# Low_Power_Brushed_Motor_Controller.net
KiCad netlist of a schematic drawn in Altium Designer
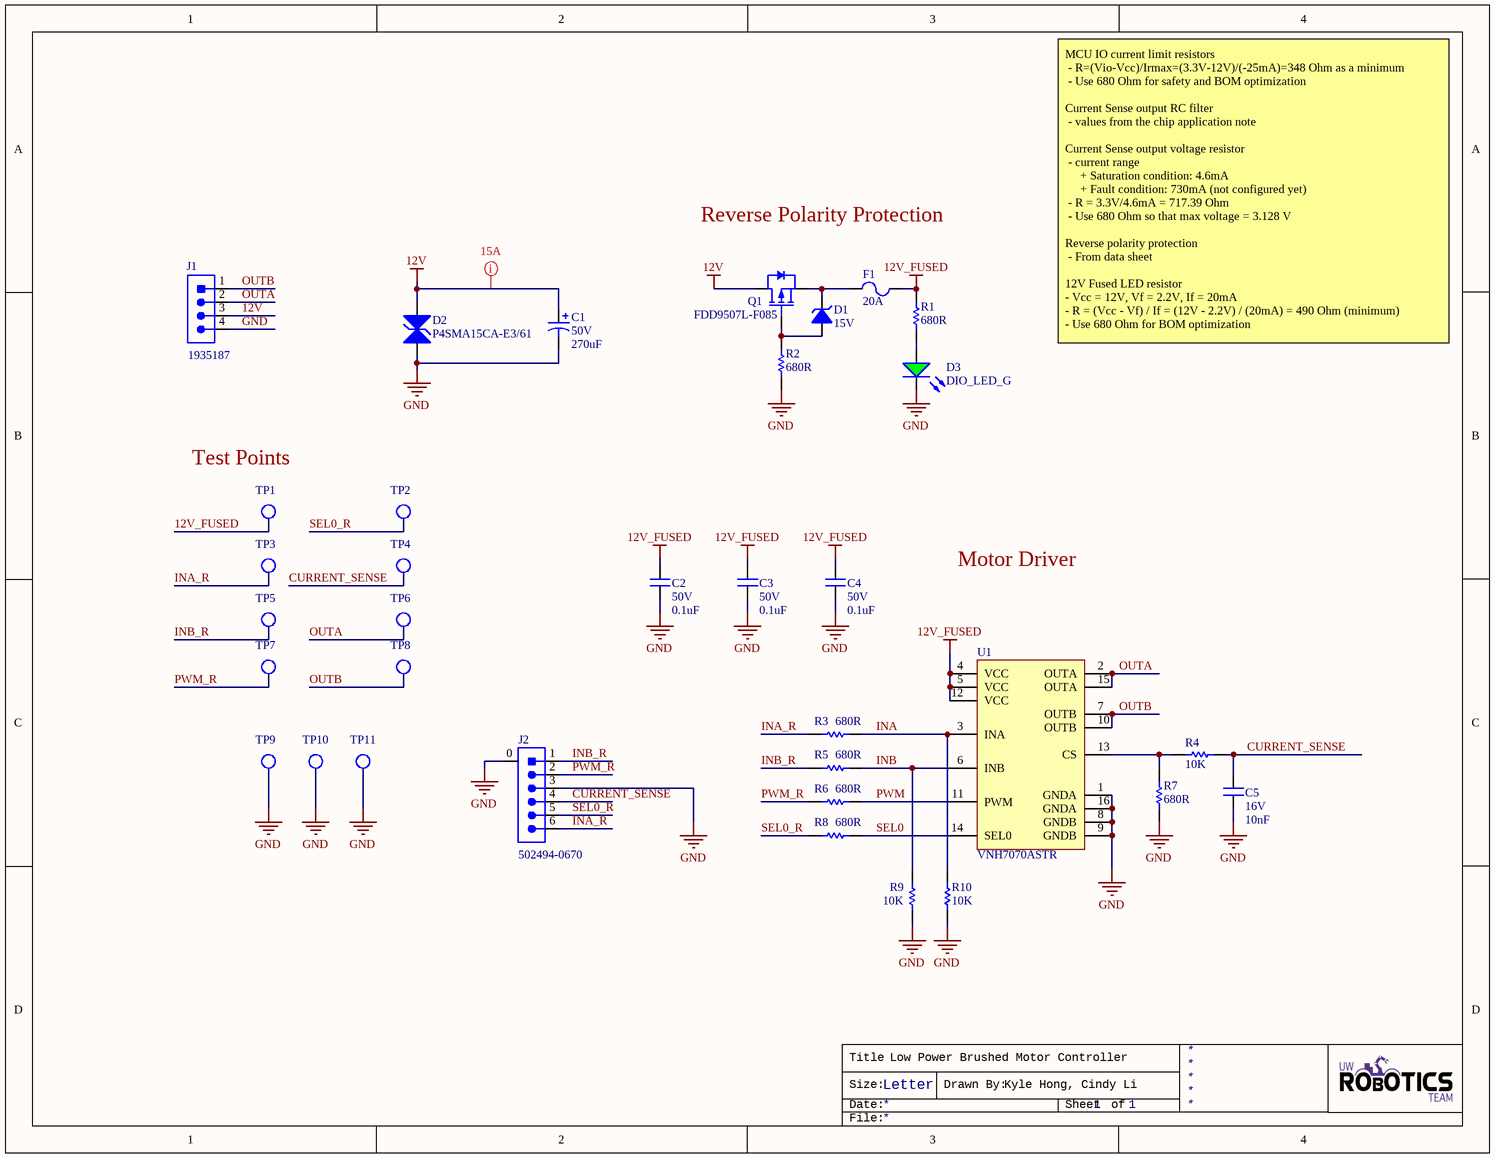
[diagram p0: Low Power Brushed Motor Controller.SchDoc]

(export (version "E")
  (design (tool "Eeschema 10.0.6"))
  (components
    (comp (ref "C1")
      (value "CAP_270uF_50V_ALUM")
      (footprint "RADIAL_PANASONIC_G")
      (description "CAP ALUM 270UF 20% 50V RADIAL")
      (fields
        (field (name "TOLERANCE") "20%")
        (field (name "VOLTAGE RATING") "50V")
        (field (name "CAPACITANCE") "270uF")
      )
      (libsource (lib "UWRT_Schematic_Library_2020") (part "CAP_270uF_50V_ALUM"))
    )
    (comp (ref "C2")
      (value "0.1uF")
      (footprint "CAPC0603(1608)55_N")
      (description "CAP CER 0.1UF 50V X7R 0603")
      (fields (field (name "VOLTAGE RATING") "50V") (field (name "Comment") "CAP_0.1uF_50V_0603"))
      (libsource (lib "UWRT_Schematic_Library_2020") (part "CAP_0.1uF_50V_0603"))
    )
    (comp (ref "C3")
      (value "0.1uF")
      (footprint "CAPC0603(1608)55_N")
      (description "CAP CER 0.1UF 50V X7R 0603")
      (fields (field (name "VOLTAGE RATING") "50V") (field (name "Comment") "CAP_0.1uF_50V_0603"))
      (libsource (lib "UWRT_Schematic_Library_2020") (part "CAP_0.1uF_50V_0603"))
    )
    (comp (ref "C4")
      (value "0.1uF")
      (footprint "CAPC0603(1608)55_N")
      (description "CAP CER 0.1UF 50V X7R 0603")
      (fields (field (name "VOLTAGE RATING") "50V") (field (name "Comment") "CAP_0.1uF_50V_0603"))
      (libsource (lib "UWRT_Schematic_Library_2020") (part "CAP_0.1uF_50V_0603"))
    )
    (comp (ref "C5")
      (value "10nF")
      (footprint "CAPC0603(1608)55_N")
      (description "CAP CER 10000PF 16V X7R 0603")
      (fields (field (name "VOLTAGE RATING") "16V") (field (name "Comment") "CAP_10nF_0603"))
      (libsource (lib "UWRT_Schematic_Library_2020") (part "CAP_10nF_0603"))
    )
    (comp (ref "D1")
      (value "DIO_ZENER_15V")
      (footprint "SOD-323_UNIDIR")
      (description "DIODE ZENER 15V 300mW SMD SOD-323")
      (fields (field (name "TOLERANCE") "5%") (field (name "WORKING VOLTAGE") "15V"))
      (libsource (lib "UWRT_Schematic_Library_2020") (part "DIO_ZENER_15V"))
    )
    (comp (ref "D2")
      (value "TVS_DIODE_BIDIR_12.8V")
      (footprint "TVS_DIODE_BIDIR_DO-214AC_SMA")
      (description "TVS DIODE 12.8V 21.2V SMA")
      (fields (field (name "MANUFACTURER PART NUMBER 1") "P4SMA15CA-E3/61"))
      (libsource (lib "UWRT_Schematic_Library_2020") (part "TVS_DIODE_BIDIR_12.8V"))
    )
    (comp (ref "D3")
      (value "DIO_LED_G")
      (footprint "LED_0805_LINE")
      (description "LED GREEN DIFFUSED 0805 SMD")
      (fields (field (name "MPN") "LG R971-KN-1") (field (name "MANUFACTURER") "OSRAM"))
      (libsource (lib "UWRT_Schematic_Library_2020") (part "DIO_LED_G"))
    )
    (comp (ref "F1")
      (value "FUSE_20A_1206")
      (footprint "FUSE_1206")
      (fields (field (name "CURRENT RATING") "20A"))
      (libsource (lib "UWRT_Schematic_Library_2020") (part "FUSE_20A_1206"))
    )
    (comp (ref "J1")
      (value "CON_4M_TERM")
      (footprint "UWRT_Footprint_Library_2020:1935187")
      (description "TERM BLK 4POS SIDE ENTRY 5MM PCB")
      (fields (field (name "MANUFACTURER PART NUMBER 1") "1935187") (field (name "VOLTAGE") "300V"))
      (libsource (lib "UWRT_Schematic_Library_2020") (part "CON_4M_TERM"))
    )
    (comp (ref "J2")
      (value "CON_6M_SM_RA")
      (footprint "MOLEX-5024940670")
      (description "CONN HEADER SMD RIGHT ANGLE 2MM PITCH")
      (fields (field (name "MANUFACTURER PART NUMBER 1") "502494-0670"))
      (libsource (lib "UWRT_Schematic_Library_2020") (part "CON_6M_SM_RA"))
    )
    (comp (ref "Q1")
      (value "PMOS_40V_100A")
      (footprint "D-PAK")
      (description "MOSFET P-CH 40V 100A D-PAK 4.4MOHM")
      (fields (field (name "MANUFACTURER PART NUMBER 1") "FDD9507L-F085"))
      (libsource (lib "UWRT_Schematic_Library_2020") (part "PMOS_40V_100A"))
    )
    (comp (ref "R1")
      (value "RES_680R_0603")
      (footprint "RESC0603(1608)_N")
      (description "RES SMD 680 OHM 5% 0.1W 0603")
      (fields (field (name "TOLERANCE") "5%") (field (name "RESISTANCE") "680R"))
      (libsource (lib "UWRT_Schematic_Library_2020") (part "RES_680R_0603"))
    )
    (comp (ref "R2")
      (value "RES_680R_0603")
      (footprint "RESC0603(1608)_N")
      (description "RES SMD 680 OHM 5% 0.1W 0603")
      (fields (field (name "TOLERANCE") "5%") (field (name "RESISTANCE") "680R"))
      (libsource (lib "UWRT_Schematic_Library_2020") (part "RES_680R_0603"))
    )
    (comp (ref "R3")
      (value "RES_680R_0603")
      (footprint "RESC0603(1608)_N")
      (description "RES SMD 680 OHM 5% 0.1W 0603")
      (fields (field (name "TOLERANCE") "5%") (field (name "RESISTANCE") "680R"))
      (libsource (lib "UWRT_Schematic_Library_2020") (part "RES_680R_0603"))
    )
    (comp (ref "R4")
      (value "10K")
      (footprint "RESC0603(1608)_N")
      (description "RES SMD 10K OHM 5% 1/10W 0603")
      (fields (field (name "TOLERANCE") "5%") (field (name "Comment") "RES_10K_0603"))
      (libsource (lib "UWRT_Schematic_Library_2020") (part "RES_10K_0603"))
    )
    (comp (ref "R5")
      (value "RES_680R_0603")
      (footprint "RESC0603(1608)_N")
      (description "RES SMD 680 OHM 5% 0.1W 0603")
      (fields (field (name "TOLERANCE") "5%") (field (name "RESISTANCE") "680R"))
      (libsource (lib "UWRT_Schematic_Library_2020") (part "RES_680R_0603"))
    )
    (comp (ref "R6")
      (value "RES_680R_0603")
      (footprint "RESC0603(1608)_N")
      (description "RES SMD 680 OHM 5% 0.1W 0603")
      (fields (field (name "TOLERANCE") "5%") (field (name "RESISTANCE") "680R"))
      (libsource (lib "UWRT_Schematic_Library_2020") (part "RES_680R_0603"))
    )
    (comp (ref "R7")
      (value "RES_680R_0603")
      (footprint "RESC0603(1608)_N")
      (description "RES SMD 680 OHM 5% 0.1W 0603")
      (fields (field (name "TOLERANCE") "5%") (field (name "RESISTANCE") "680R"))
      (libsource (lib "UWRT_Schematic_Library_2020") (part "RES_680R_0603"))
    )
    (comp (ref "R8")
      (value "RES_680R_0603")
      (footprint "RESC0603(1608)_N")
      (description "RES SMD 680 OHM 5% 0.1W 0603")
      (fields (field (name "TOLERANCE") "5%") (field (name "RESISTANCE") "680R"))
      (libsource (lib "UWRT_Schematic_Library_2020") (part "RES_680R_0603"))
    )
    (comp (ref "R9")
      (value "10K")
      (footprint "RESC0603(1608)_N")
      (description "RES SMD 10K OHM 5% 1/10W 0603")
      (fields (field (name "TOLERANCE") "5%") (field (name "Comment") "RES_10K_0603"))
      (libsource (lib "UWRT_Schematic_Library_2020") (part "RES_10K_0603"))
    )
    (comp (ref "R10")
      (value "10K")
      (footprint "RESC0603(1608)_N")
      (description "RES SMD 10K OHM 5% 1/10W 0603")
      (fields (field (name "TOLERANCE") "5%") (field (name "Comment") "RES_10K_0603"))
      (libsource (lib "UWRT_Schematic_Library_2020") (part "RES_10K_0603"))
    )
    (comp (ref "TP1")
      (value "TESTPOINT_LOOP")
      (footprint "TESTPOINT_LOOP")
      (description "Loop testpoint through-hole pad")
      (fields (field (name "MANUFACTURER") "Keystone Electronics"))
      (libsource (lib "UWRT_Schematic_Library_2020") (part "TESTPOINT_LOOP"))
    )
    (comp (ref "TP2")
      (value "TESTPOINT_LOOP")
      (footprint "TESTPOINT_LOOP")
      (description "Loop testpoint through-hole pad")
      (fields (field (name "MANUFACTURER") "Keystone Electronics"))
      (libsource (lib "UWRT_Schematic_Library_2020") (part "TESTPOINT_LOOP"))
    )
    (comp (ref "TP3")
      (value "TESTPOINT_LOOP")
      (footprint "TESTPOINT_LOOP")
      (description "Loop testpoint through-hole pad")
      (fields (field (name "MANUFACTURER") "Keystone Electronics"))
      (libsource (lib "UWRT_Schematic_Library_2020") (part "TESTPOINT_LOOP"))
    )
    (comp (ref "TP4")
      (value "TESTPOINT_LOOP")
      (footprint "TESTPOINT_LOOP")
      (description "Loop testpoint through-hole pad")
      (fields (field (name "MANUFACTURER") "Keystone Electronics"))
      (libsource (lib "UWRT_Schematic_Library_2020") (part "TESTPOINT_LOOP"))
    )
    (comp (ref "TP5")
      (value "TESTPOINT_LOOP")
      (footprint "TESTPOINT_LOOP")
      (description "Loop testpoint through-hole pad")
      (fields (field (name "MANUFACTURER") "Keystone Electronics"))
      (libsource (lib "UWRT_Schematic_Library_2020") (part "TESTPOINT_LOOP"))
    )
    (comp (ref "TP6")
      (value "TESTPOINT_LOOP")
      (footprint "TESTPOINT_LOOP")
      (description "Loop testpoint through-hole pad")
      (fields (field (name "MANUFACTURER") "Keystone Electronics"))
      (libsource (lib "UWRT_Schematic_Library_2020") (part "TESTPOINT_LOOP"))
    )
    (comp (ref "TP7")
      (value "TESTPOINT_LOOP")
      (footprint "TESTPOINT_LOOP")
      (description "Loop testpoint through-hole pad")
      (fields (field (name "MANUFACTURER") "Keystone Electronics"))
      (libsource (lib "UWRT_Schematic_Library_2020") (part "TESTPOINT_LOOP"))
    )
    (comp (ref "TP8")
      (value "TESTPOINT_LOOP")
      (footprint "TESTPOINT_LOOP")
      (description "Loop testpoint through-hole pad")
      (fields (field (name "MANUFACTURER") "Keystone Electronics"))
      (libsource (lib "UWRT_Schematic_Library_2020") (part "TESTPOINT_LOOP"))
    )
    (comp (ref "TP9")
      (value "TESTPOINT_LOOP")
      (footprint "TESTPOINT_LOOP")
      (description "Loop testpoint through-hole pad")
      (fields (field (name "MANUFACTURER") "Keystone Electronics"))
      (libsource (lib "UWRT_Schematic_Library_2020") (part "TESTPOINT_LOOP"))
    )
    (comp (ref "TP10")
      (value "TESTPOINT_LOOP")
      (footprint "TESTPOINT_LOOP")
      (description "Loop testpoint through-hole pad")
      (fields (field (name "MANUFACTURER") "Keystone Electronics"))
      (libsource (lib "UWRT_Schematic_Library_2020") (part "TESTPOINT_LOOP"))
    )
    (comp (ref "TP11")
      (value "TESTPOINT_LOOP")
      (footprint "TESTPOINT_LOOP")
      (description "Loop testpoint through-hole pad")
      (fields (field (name "MANUFACTURER") "Keystone Electronics"))
      (libsource (lib "UWRT_Schematic_Library_2020") (part "TESTPOINT_LOOP"))
    )
    (comp (ref "U1")
      (value "IC_MOTOR_DRIVER_ST")
      (footprint "SO-16N")
      (description "IC H-BRIDGE MOTOR DRIVER 16-PINS STMicroelectronics VNH7070ASTR, SOIC")
      (fields (field (name "MANUFACTURER PART NUMBER 1") "VNH7070ASTR"))
      (libsource (lib "UWRT_Schematic_Library_2020") (part "IC_MOTOR_DRIVER_ST"))
    )
  )
  (nets
    (net (code "1") (name "/CURRENT_SENSE") (class "Default")
      (node (ref "C5") (pin "2") (pinfunction "2_2") (pintype "passive"))
      (node (ref "J2") (pin "4") (pinfunction "4_4") (pintype "passive"))
      (node (ref "R4") (pin "2") (pinfunction "2_2") (pintype "passive"))
      (node (ref "TP4") (pin "1") (pintype "passive"))
    )
    (net (code "2") (name "/INA") (class "Default")
      (node (ref "R10") (pin "2") (pinfunction "2_2") (pintype "passive"))
      (node (ref "R3") (pin "2") (pinfunction "2_2") (pintype "passive"))
      (node (ref "U1") (pin "3") (pinfunction "INA_3") (pintype "passive"))
    )
    (net (code "3") (name "/INA_R") (class "Default")
      (node (ref "J2") (pin "6") (pinfunction "6_6") (pintype "passive"))
      (node (ref "R3") (pin "1") (pinfunction "1_1") (pintype "passive"))
      (node (ref "TP3") (pin "1") (pintype "passive"))
    )
    (net (code "4") (name "/INB") (class "Default")
      (node (ref "R5") (pin "2") (pinfunction "2_2") (pintype "passive"))
      (node (ref "R9") (pin "2") (pinfunction "2_2") (pintype "passive"))
      (node (ref "U1") (pin "6") (pinfunction "INB_6") (pintype "passive"))
    )
    (net (code "5") (name "/INB_R") (class "Default")
      (node (ref "J2") (pin "1") (pinfunction "1_1") (pintype "passive"))
      (node (ref "R5") (pin "1") (pinfunction "1_1") (pintype "passive"))
      (node (ref "TP5") (pin "1") (pintype "passive"))
    )
    (net (code "6") (name "/OUTA") (class "Default")
      (node (ref "J1") (pin "2") (pinfunction "2_2") (pintype "passive"))
      (node (ref "TP6") (pin "1") (pintype "passive"))
      (node (ref "U1") (pin "15") (pinfunction "OUTA_15") (pintype "passive"))
      (node (ref "U1") (pin "2") (pinfunction "OUTA_2") (pintype "passive"))
    )
    (net (code "7") (name "/OUTB") (class "Default")
      (node (ref "J1") (pin "1") (pinfunction "1_1") (pintype "passive"))
      (node (ref "TP8") (pin "1") (pintype "passive"))
      (node (ref "U1") (pin "10") (pinfunction "OUTB_10") (pintype "passive"))
      (node (ref "U1") (pin "7") (pinfunction "OUTB_7") (pintype "passive"))
    )
    (net (code "8") (name "/PWM") (class "Default")
      (node (ref "R6") (pin "2") (pinfunction "2_2") (pintype "passive"))
      (node (ref "U1") (pin "11") (pinfunction "PWM_11") (pintype "passive"))
    )
    (net (code "9") (name "/PWM_R") (class "Default")
      (node (ref "J2") (pin "2") (pinfunction "2_2") (pintype "passive"))
      (node (ref "R6") (pin "1") (pinfunction "1_1") (pintype "passive"))
      (node (ref "TP7") (pin "1") (pintype "passive"))
    )
    (net (code "10") (name "/SEL0") (class "Default")
      (node (ref "R8") (pin "2") (pinfunction "2_2") (pintype "passive"))
      (node (ref "U1") (pin "14") (pinfunction "SEL0_14") (pintype "passive"))
    )
    (net (code "11") (name "/SEL0_R") (class "Default")
      (node (ref "J2") (pin "5") (pinfunction "5_5") (pintype "passive"))
      (node (ref "R8") (pin "1") (pinfunction "1_1") (pintype "passive"))
      (node (ref "TP2") (pin "1") (pintype "passive"))
    )
    (net (code "12") (name "12V") (class "Default")
      (node (ref "C1") (pin "1") (pinfunction "1_1") (pintype "passive"))
      (node (ref "D2") (pin "1") (pinfunction "1_1") (pintype "passive"))
      (node (ref "J1") (pin "3") (pinfunction "3_3") (pintype "passive"))
      (node (ref "Q1") (pin "2") (pinfunction "Drain_2") (pintype "passive"))
    )
    (net (code "13") (name "12V_FUSED") (class "Default")
      (node (ref "C2") (pin "2") (pinfunction "2_2") (pintype "passive"))
      (node (ref "C3") (pin "2") (pinfunction "2_2") (pintype "passive"))
      (node (ref "C4") (pin "1") (pinfunction "1_1") (pintype "passive"))
      (node (ref "F1") (pin "2") (pinfunction "2_2") (pintype "passive"))
      (node (ref "R1") (pin "2") (pinfunction "2_2") (pintype "passive"))
      (node (ref "TP1") (pin "1") (pintype "passive"))
      (node (ref "U1") (pin "12") (pinfunction "VCC_12") (pintype "power_in"))
      (node (ref "U1") (pin "4") (pinfunction "VCC_4") (pintype "power_in"))
      (node (ref "U1") (pin "5") (pinfunction "VCC_5") (pintype "power_in"))
    )
    (net (code "14") (name "GND") (class "Default")
      (node (ref "C1") (pin "2") (pinfunction "2_2") (pintype "passive"))
      (node (ref "C2") (pin "1") (pinfunction "1_1") (pintype "passive"))
      (node (ref "C3") (pin "1") (pinfunction "1_1") (pintype "passive"))
      (node (ref "C4") (pin "2") (pinfunction "2_2") (pintype "passive"))
      (node (ref "C5") (pin "1") (pinfunction "1_1") (pintype "passive"))
      (node (ref "D2") (pin "2") (pinfunction "2_2") (pintype "passive"))
      (node (ref "D3") (pin "2") (pinfunction "K_2") (pintype "passive"))
      (node (ref "J1") (pin "4") (pinfunction "4_4") (pintype "passive"))
      (node (ref "J2") (pin "0") (pinfunction "0_0") (pintype "passive"))
      (node (ref "J2") (pin "3") (pinfunction "3_3") (pintype "passive"))
      (node (ref "R10") (pin "1") (pinfunction "1_1") (pintype "passive"))
      (node (ref "R2") (pin "1") (pinfunction "1_1") (pintype "passive"))
      (node (ref "R7") (pin "1") (pinfunction "1_1") (pintype "passive"))
      (node (ref "R9") (pin "1") (pinfunction "1_1") (pintype "passive"))
      (node (ref "TP10") (pin "1") (pintype "passive"))
      (node (ref "TP11") (pin "1") (pintype "passive"))
      (node (ref "TP9") (pin "1") (pintype "passive"))
      (node (ref "U1") (pin "1") (pinfunction "GNDA_1") (pintype "power_in"))
      (node (ref "U1") (pin "16") (pinfunction "GNDA_16") (pintype "power_in"))
      (node (ref "U1") (pin "8") (pinfunction "GNDB_8") (pintype "power_in"))
      (node (ref "U1") (pin "9") (pinfunction "GNDB_9") (pintype "power_in"))
    )
    (net (code "15") (name "Net-(D1-Anode)") (class "Default")
      (node (ref "D1") (pin "1") (pinfunction "Anode_1") (pintype "passive"))
      (node (ref "Q1") (pin "1") (pinfunction "Gate_1") (pintype "passive"))
      (node (ref "R2") (pin "2") (pinfunction "2_2") (pintype "passive"))
    )
    (net (code "16") (name "Net-(D1-Cathode)") (class "Default")
      (node (ref "D1") (pin "2") (pinfunction "Cathode_2") (pintype "passive"))
      (node (ref "F1") (pin "1") (pinfunction "1_1") (pintype "passive"))
      (node (ref "Q1") (pin "3") (pinfunction "Source_3") (pintype "passive"))
    )
    (net (code "17") (name "Net-(D3-A)") (class "Default")
      (node (ref "D3") (pin "1") (pinfunction "A_1") (pintype "passive"))
      (node (ref "R1") (pin "1") (pinfunction "1_1") (pintype "passive"))
    )
    (net (code "18") (name "Net-(U1-CS)") (class "Default")
      (node (ref "R4") (pin "1") (pinfunction "1_1") (pintype "passive"))
      (node (ref "R7") (pin "2") (pinfunction "2_2") (pintype "passive"))
      (node (ref "U1") (pin "13") (pinfunction "CS_13") (pintype "passive"))
    )
  )
)
